# msp430-cc2500_breakout.net
KiCad netlist of a schematic drawn in EAGLE
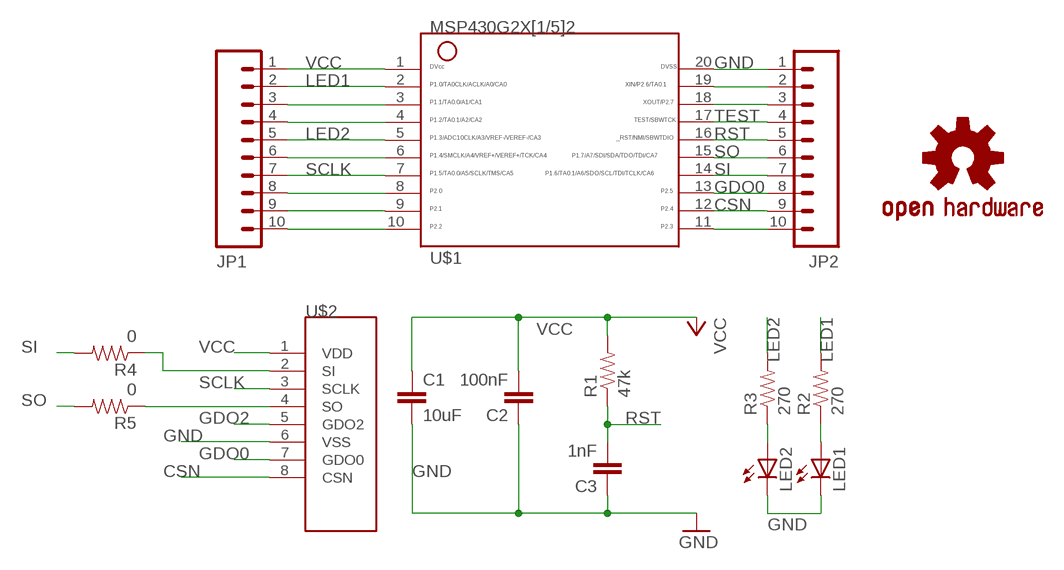
[diagram p0: schematic, sheet 1]

(export (version "E")
  (design (tool "Eeschema 10.0.6"))
  (components
    (comp (ref "C1")
      (value "10uF")
      (footprint "eagle-import:0805")
      (libsource (lib "eagle-import") (part "CAP0805"))
    )
    (comp (ref "C2")
      (value "100nF")
      (footprint "eagle-import:0805")
      (libsource (lib "eagle-import") (part "CAP0805"))
    )
    (comp (ref "C3")
      (value "1nF")
      (footprint "eagle-import:0805")
      (libsource (lib "eagle-import") (part "CAP0805"))
    )
    (comp (ref "JP1")
      (value "M10\"")
      (footprint "eagle-import:1X10")
      (libsource (lib "eagle-import") (part "M10{dblquote}"))
    )
    (comp (ref "JP2")
      (value "M10\"")
      (footprint "eagle-import:1X10")
      (libsource (lib "eagle-import") (part "M10{dblquote}"))
    )
    (comp (ref "LED1")
      (value "LED1206")
      (footprint "eagle-import:LED-1206")
      (libsource (lib "eagle-import") (part "LED1206"))
    )
    (comp (ref "LED2")
      (value "LED1206")
      (footprint "eagle-import:LED-1206")
      (libsource (lib "eagle-import") (part "LED1206"))
    )
    (comp (ref "R1")
      (value "47k")
      (footprint "eagle-import:0805")
      (libsource (lib "eagle-import") (part "RESISTOR0805-RES"))
    )
    (comp (ref "R2")
      (value "270")
      (footprint "eagle-import:0805")
      (libsource (lib "eagle-import") (part "RESISTOR0805-RES"))
    )
    (comp (ref "R3")
      (value "270")
      (footprint "eagle-import:0805")
      (libsource (lib "eagle-import") (part "RESISTOR0805-RES"))
    )
    (comp (ref "R4")
      (value "0")
      (footprint "eagle-import:0805")
      (libsource (lib "eagle-import") (part "RESISTOR0805-RES"))
    )
    (comp (ref "R5")
      (value "0")
      (footprint "eagle-import:0805")
      (libsource (lib "eagle-import") (part "RESISTOR0805-RES"))
    )
    (comp (ref "U$1")
      (value "G2X[1/5]2---PW20")
      (footprint "eagle-import:PW20")
      (libsource (lib "eagle-import") (part "G2X[1/5]2---PW20"))
    )
    (comp (ref "U$2")
      (value "CC2500-MODULESMT")
      (footprint "eagle-import:CC2500-MODULE-SMT")
      (libsource (lib "eagle-import") (part "CC2500-MODULESMT"))
    )
    (comp (ref "U$3")
      (value "OSHW-LOGOL")
      (footprint "eagle-import:OSHW-LOGO-L")
      (libsource (lib "eagle-import") (part "OSHW-LOGOL"))
    )
  )
  (nets
    (net (code "1") (name "/CSN") (class "Default")
      (node (ref "JP2") (pin "9") (pinfunction "9_9") (pintype "passive"))
      (node (ref "U$1") (pin "12") (pinfunction "12_12") (pintype "bidirectional"))
      (node (ref "U$2") (pin "8") (pinfunction "CSN_8") (pintype "bidirectional"))
    )
    (net (code "2") (name "/GDO0") (class "Default")
      (node (ref "JP2") (pin "8") (pinfunction "8_8") (pintype "passive"))
      (node (ref "U$1") (pin "13") (pinfunction "13_13") (pintype "bidirectional"))
      (node (ref "U$2") (pin "7") (pinfunction "GDO0_7") (pintype "bidirectional"))
    )
    (net (code "3") (name "/GDO2") (class "Default")
      (node (ref "U$2") (pin "5") (pinfunction "GDO2_5") (pintype "bidirectional"))
    )
    (net (code "4") (name "/LED1") (class "Default")
      (node (ref "JP1") (pin "2") (pinfunction "2_2") (pintype "passive"))
      (node (ref "R2") (pin "2") (pinfunction "2_2") (pintype "passive"))
      (node (ref "U$1") (pin "2") (pinfunction "2_2") (pintype "bidirectional"))
    )
    (net (code "5") (name "/LED2") (class "Default")
      (node (ref "JP1") (pin "5") (pinfunction "5_5") (pintype "passive"))
      (node (ref "R3") (pin "2") (pinfunction "2_2") (pintype "passive"))
      (node (ref "U$1") (pin "5") (pinfunction "5_5") (pintype "bidirectional"))
    )
    (net (code "6") (name "/RST") (class "Default")
      (node (ref "C3") (pin "2") (pinfunction "2_2") (pintype "passive"))
      (node (ref "JP2") (pin "5") (pinfunction "5_5") (pintype "passive"))
      (node (ref "R1") (pin "1") (pinfunction "1_1") (pintype "passive"))
      (node (ref "U$1") (pin "16") (pinfunction "16_16") (pintype "bidirectional"))
    )
    (net (code "7") (name "/SCLK") (class "Default")
      (node (ref "JP1") (pin "7") (pinfunction "7_7") (pintype "passive"))
      (node (ref "U$1") (pin "7") (pinfunction "7_7") (pintype "bidirectional"))
      (node (ref "U$2") (pin "3") (pinfunction "SCLK_3") (pintype "bidirectional"))
    )
    (net (code "8") (name "/SI") (class "Default")
      (node (ref "JP2") (pin "7") (pinfunction "7_7") (pintype "passive"))
      (node (ref "R4") (pin "2") (pinfunction "2_2") (pintype "passive"))
      (node (ref "U$1") (pin "14") (pinfunction "14_14") (pintype "bidirectional"))
    )
    (net (code "9") (name "/SO") (class "Default")
      (node (ref "JP2") (pin "6") (pinfunction "6_6") (pintype "passive"))
      (node (ref "R5") (pin "2") (pinfunction "2_2") (pintype "passive"))
      (node (ref "U$1") (pin "15") (pinfunction "15_15") (pintype "bidirectional"))
    )
    (net (code "10") (name "/TEST") (class "Default")
      (node (ref "JP2") (pin "4") (pinfunction "4_4") (pintype "passive"))
      (node (ref "U$1") (pin "17") (pinfunction "17_17") (pintype "bidirectional"))
    )
    (net (code "11") (name "GND") (class "Default")
      (node (ref "C1") (pin "2") (pinfunction "2_2") (pintype "passive"))
      (node (ref "C2") (pin "1") (pinfunction "1_1") (pintype "passive"))
      (node (ref "C3") (pin "1") (pinfunction "1_1") (pintype "passive"))
      (node (ref "JP2") (pin "1") (pinfunction "1_1") (pintype "passive"))
      (node (ref "LED1") (pin "C") (pinfunction "C_C") (pintype "passive"))
      (node (ref "LED2") (pin "C") (pinfunction "C_C") (pintype "passive"))
      (node (ref "U$1") (pin "20") (pinfunction "20_20") (pintype "bidirectional"))
      (node (ref "U$2") (pin "6") (pinfunction "VSS_6") (pintype "bidirectional"))
    )
    (net (code "12") (name "Net-(JP1-Pad3)") (class "Default")
      (node (ref "JP1") (pin "3") (pinfunction "3_3") (pintype "passive"))
      (node (ref "U$1") (pin "3") (pinfunction "3_3") (pintype "bidirectional"))
    )
    (net (code "13") (name "Net-(JP1-Pad4)") (class "Default")
      (node (ref "JP1") (pin "4") (pinfunction "4_4") (pintype "passive"))
      (node (ref "U$1") (pin "4") (pinfunction "4_4") (pintype "bidirectional"))
    )
    (net (code "14") (name "Net-(JP1-Pad6)") (class "Default")
      (node (ref "JP1") (pin "6") (pinfunction "6_6") (pintype "passive"))
      (node (ref "U$1") (pin "6") (pinfunction "6_6") (pintype "bidirectional"))
    )
    (net (code "15") (name "Net-(JP1-Pad8)") (class "Default")
      (node (ref "JP1") (pin "8") (pinfunction "8_8") (pintype "passive"))
      (node (ref "U$1") (pin "8") (pinfunction "8_8") (pintype "bidirectional"))
    )
    (net (code "16") (name "Net-(JP1-Pad9)") (class "Default")
      (node (ref "JP1") (pin "9") (pinfunction "9_9") (pintype "passive"))
      (node (ref "U$1") (pin "9") (pinfunction "9_9") (pintype "bidirectional"))
    )
    (net (code "17") (name "Net-(JP1-Pad10)") (class "Default")
      (node (ref "JP1") (pin "10") (pinfunction "10_10") (pintype "passive"))
      (node (ref "U$1") (pin "10") (pinfunction "10_10") (pintype "bidirectional"))
    )
    (net (code "18") (name "Net-(JP2-Pad2)") (class "Default")
      (node (ref "JP2") (pin "2") (pinfunction "2_2") (pintype "passive"))
      (node (ref "U$1") (pin "19") (pinfunction "19_19") (pintype "bidirectional"))
    )
    (net (code "19") (name "Net-(JP2-Pad3)") (class "Default")
      (node (ref "JP2") (pin "3") (pinfunction "3_3") (pintype "passive"))
      (node (ref "U$1") (pin "18") (pinfunction "18_18") (pintype "bidirectional"))
    )
    (net (code "20") (name "Net-(JP2-Pad10)") (class "Default")
      (node (ref "JP2") (pin "10") (pinfunction "10_10") (pintype "passive"))
      (node (ref "U$1") (pin "11") (pinfunction "11_11") (pintype "bidirectional"))
    )
    (net (code "21") (name "Net-(LED1-PadA)") (class "Default")
      (node (ref "LED1") (pin "A") (pinfunction "A_A") (pintype "passive"))
      (node (ref "R2") (pin "1") (pinfunction "1_1") (pintype "passive"))
    )
    (net (code "22") (name "Net-(LED2-PadA)") (class "Default")
      (node (ref "LED2") (pin "A") (pinfunction "A_A") (pintype "passive"))
      (node (ref "R3") (pin "1") (pinfunction "1_1") (pintype "passive"))
    )
    (net (code "23") (name "Net-(U$2-SI)") (class "Default")
      (node (ref "R4") (pin "1") (pinfunction "1_1") (pintype "passive"))
      (node (ref "U$2") (pin "2") (pinfunction "SI_2") (pintype "bidirectional"))
    )
    (net (code "24") (name "Net-(U$2-SO)") (class "Default")
      (node (ref "R5") (pin "1") (pinfunction "1_1") (pintype "passive"))
      (node (ref "U$2") (pin "4") (pinfunction "SO_4") (pintype "bidirectional"))
    )
    (net (code "25") (name "VCC") (class "Default")
      (node (ref "C1") (pin "1") (pinfunction "1_1") (pintype "passive"))
      (node (ref "C2") (pin "2") (pinfunction "2_2") (pintype "passive"))
      (node (ref "JP1") (pin "1") (pinfunction "1_1") (pintype "passive"))
      (node (ref "R1") (pin "2") (pinfunction "2_2") (pintype "passive"))
      (node (ref "U$1") (pin "1") (pinfunction "1_1") (pintype "bidirectional"))
      (node (ref "U$2") (pin "1") (pinfunction "VDD_1") (pintype "bidirectional"))
    )
  )
)
